# Heartbeat_sch.net
KiCad netlist of a schematic drawn in Altium Designer
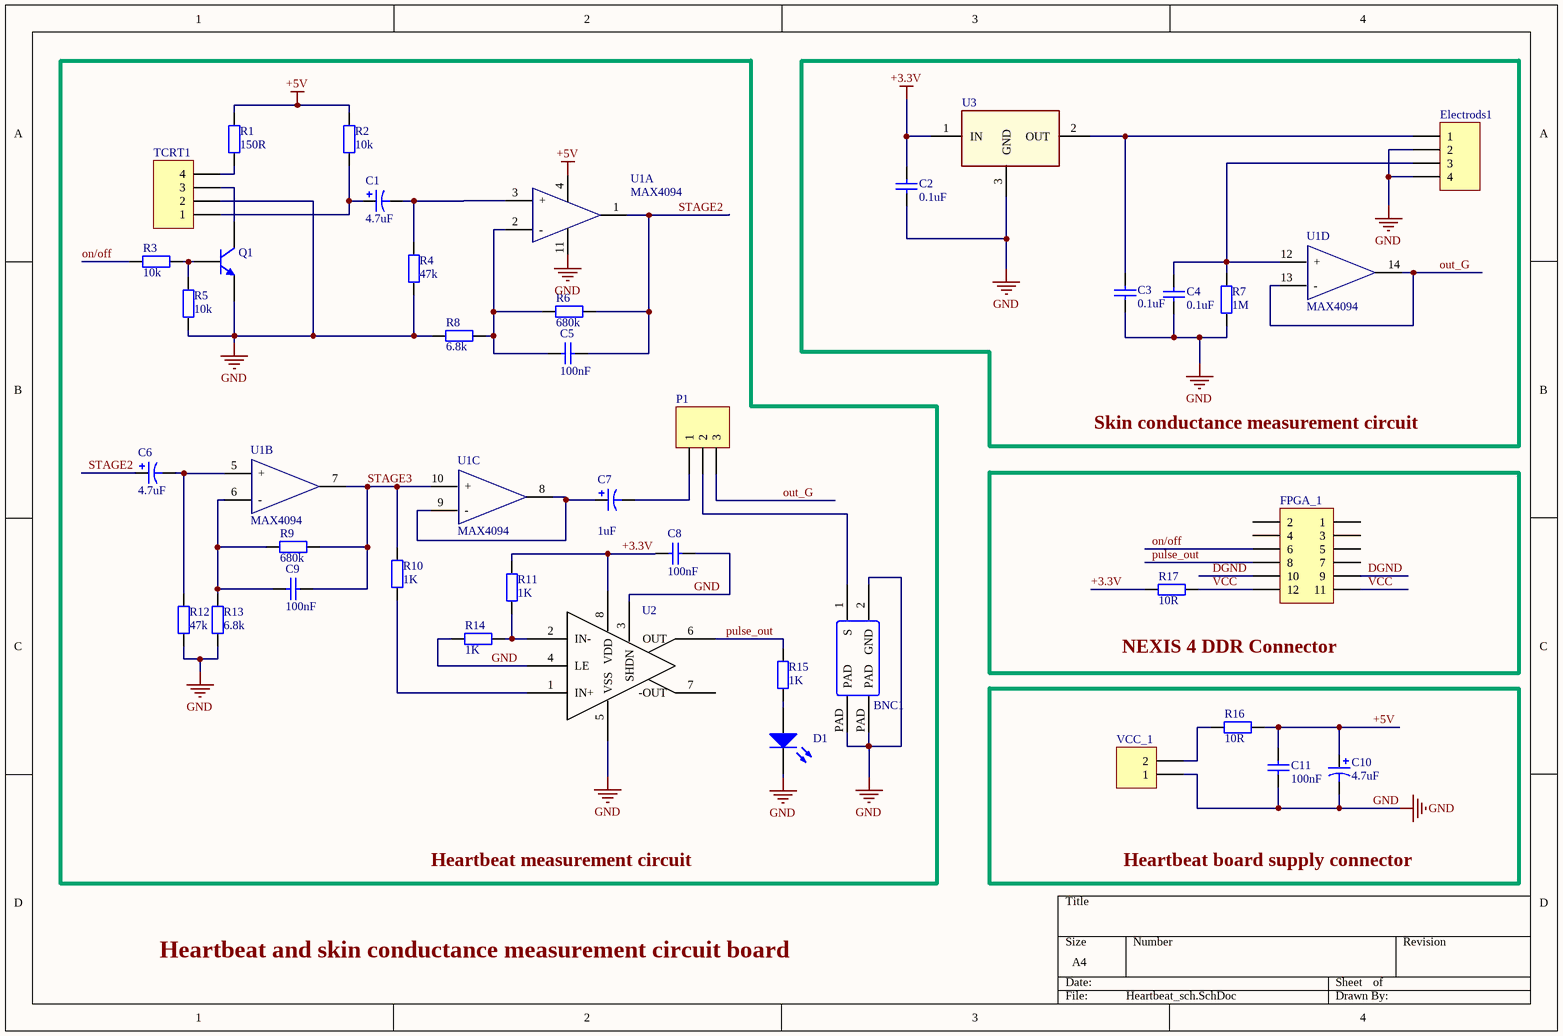
[diagram p0: Heartbeat_sch.SchDoc]

(export (version "E")
  (design (tool "Eeschema 10.0.6"))
  (components
    (comp (ref "BNC1")
      (value "BNC FEMALE CONN")
      (footprint "BNC CONNECTOR")
      (libsource (lib "BNC PCB CONN") (part "BNC FEMALE CONN"))
    )
    (comp (ref "C1")
      (value "4.7uF")
      (footprint "Condensator SMD tantal case A")
      (description "Polarized Capacitor (Radial)")
      (fields (field (name "Comment") "Cap Pol1") (field (name "PUBLISHER") "Altium Limited"))
      (libsource (lib "Miscellaneous Devices") (part "Cap Pol1"))
    )
    (comp (ref "C2")
      (value "0.1uF")
      (footprint "capacitor 2012[0805]:capacitor 2012[0805]")
      (description "Capacitor")
      (fields (field (name "Comment") "Cap") (field (name "PUBLISHER") "Altium Limited"))
      (libsource (lib "Miscellaneous Devices") (part "Cap"))
    )
    (comp (ref "C3")
      (value "0.1uF")
      (footprint "capacitor 2012[0805]:capacitor 2012[0805]")
      (description "Capacitor")
      (fields (field (name "Comment") "Cap") (field (name "PUBLISHER") "Altium Limited"))
      (libsource (lib "Miscellaneous Devices") (part "Cap"))
    )
    (comp (ref "C4")
      (value "0.1uF")
      (footprint "capacitor 2012[0805]:capacitor 2012[0805]")
      (description "Capacitor")
      (fields (field (name "Comment") "Cap") (field (name "PUBLISHER") "Altium Limited"))
      (libsource (lib "Miscellaneous Devices") (part "Cap"))
    )
    (comp (ref "C5")
      (value "100nF")
      (footprint "capacitor 2012[0805]:capacitor 2012[0805]")
      (description "Capacitor")
      (fields (field (name "Comment") "Cap") (field (name "PUBLISHER") "Altium Limited"))
      (libsource (lib "Miscellaneous Devices") (part "Cap"))
    )
    (comp (ref "C6")
      (value "4.7uF")
      (footprint "Condensator SMD tantal case A")
      (description "Polarized Capacitor (Radial)")
      (fields (field (name "Comment") "Cap Pol1") (field (name "PUBLISHER") "Altium Limited"))
      (libsource (lib "Miscellaneous Devices") (part "Cap Pol1"))
    )
    (comp (ref "C7")
      (value "1uF")
      (footprint "Condensator SMD tantal case A")
      (description "Polarized Capacitor (Radial)")
      (fields (field (name "Comment") "Cap Pol1") (field (name "PUBLISHER") "Altium Limited"))
      (libsource (lib "Miscellaneous Devices") (part "Cap Pol1"))
    )
    (comp (ref "C8")
      (value "100nF")
      (footprint "capacitor 2012[0805]:capacitor 2012[0805]")
      (description "Capacitor")
      (fields (field (name "Comment") "Cap") (field (name "PUBLISHER") "Altium Limited"))
      (libsource (lib "Miscellaneous Devices") (part "Cap"))
    )
    (comp (ref "C9")
      (value "100nF")
      (footprint "capacitor 2012[0805]:capacitor 2012[0805]")
      (description "Capacitor")
      (fields (field (name "Comment") "Cap") (field (name "PUBLISHER") "Altium Limited"))
      (libsource (lib "Miscellaneous Devices") (part "Cap"))
    )
    (comp (ref "C10")
      (value "4.7uF")
      (footprint "Condensator SMD tantal case A")
      (description "Polarized Capacitor (Radial)")
      (fields (field (name "Comment") "Cap Pol1") (field (name "PUBLISHER") "Altium Limited"))
      (libsource (lib "Miscellaneous Devices") (part "Cap Pol1"))
    )
    (comp (ref "C11")
      (value "100nF")
      (footprint "capacitor 2012[0805]:capacitor 2012[0805]")
      (description "Capacitor")
      (fields (field (name "Comment") "Cap") (field (name "PUBLISHER") "Altium Limited"))
      (libsource (lib "Miscellaneous Devices") (part "Cap"))
    )
    (comp (ref "D1")
      (value "LED0")
      (footprint "led smd verde:led smd verde")
      (description "Typical INFRARED GaAs LED")
      (fields (field (name "PUBLISHER") "Altium Limited"))
      (libsource (lib "Miscellaneous Devices") (part "LED0"))
    )
    (comp (ref "Electrods1")
      (value "Header 4H")
      (footprint "HDR1X4H")
      (description "Header, 4-Pin, Right Angle")
      (fields (field (name "PUBLISHER") "Altium Limited"))
      (libsource (lib "") (part "Header 4H_1"))
    )
    (comp (ref "FPGA_1")
      (value "Header 6X2H")
      (footprint "HDR2X6H")
      (description "Header, 6-Pin, Dual row, Right Angle")
      (fields (field (name "PUBLISHER") "Altium Limited"))
      (libsource (lib "Miscellaneous Connectors") (part "Header 6X2H"))
    )
    (comp (ref "P1")
      (value "Header 3")
      (footprint "hdr x3male:hdr3")
      (description "Header, 3-Pin")
      (fields (field (name "PUBLISHER") "Altium Limited"))
      (libsource (lib "Miscellaneous Connectors") (part "Header 3"))
    )
    (comp (ref "Q1")
      (value "2N3904")
      (footprint "SOT23-3M")
      (description "NPN General Purpose Amplifier")
      (fields (field (name "PUBLISHER") "Altium Limited"))
      (libsource (lib "Miscellaneous Devices") (part "2N3904"))
    )
    (comp (ref "R1")
      (value "150R")
      (footprint "2012 (Rezistor):2012(rezistor)")
      (description "Resistor")
      (fields (field (name "Comment") "Res2") (field (name "PUBLISHER") "Altium Limited"))
      (libsource (lib "") (part "Res2_1"))
    )
    (comp (ref "R2")
      (value "10k")
      (footprint "2012 (Rezistor):2012(rezistor)")
      (description "Resistor")
      (fields (field (name "Comment") "Res2") (field (name "PUBLISHER") "Altium Limited"))
      (libsource (lib "") (part "Res2_1"))
    )
    (comp (ref "R3")
      (value "10k")
      (footprint "2012 (Rezistor):2012(rezistor)")
      (description "Resistor")
      (fields (field (name "Comment") "Res2") (field (name "PUBLISHER") "Altium Limited"))
      (libsource (lib "Miscellaneous Devices") (part "Res2"))
    )
    (comp (ref "R4")
      (value "47k")
      (footprint "2012 (Rezistor):2012(rezistor)")
      (description "Resistor")
      (fields (field (name "Comment") "Res2") (field (name "PUBLISHER") "Altium Limited"))
      (libsource (lib "") (part "Res2_2"))
    )
    (comp (ref "R5")
      (value "10k")
      (footprint "2012 (Rezistor):2012(rezistor)")
      (description "Resistor")
      (fields (field (name "Comment") "Res2") (field (name "PUBLISHER") "Altium Limited"))
      (libsource (lib "") (part "Res2_1"))
    )
    (comp (ref "R6")
      (value "680k")
      (footprint "2012 (Rezistor):2012(rezistor)")
      (description "Resistor")
      (fields (field (name "Comment") "Res2") (field (name "PUBLISHER") "Altium Limited"))
      (libsource (lib "Miscellaneous Devices") (part "Res2"))
    )
    (comp (ref "R7")
      (value "1M")
      (footprint "2012 (Rezistor):2012(rezistor)")
      (description "Resistor")
      (fields (field (name "Comment") "Res2") (field (name "PUBLISHER") "Altium Limited"))
      (libsource (lib "") (part "Res2_1"))
    )
    (comp (ref "R8")
      (value "6.8k")
      (footprint "2012 (Rezistor):2012(rezistor)")
      (description "Resistor")
      (fields (field (name "Comment") "Res2") (field (name "PUBLISHER") "Altium Limited"))
      (libsource (lib "Miscellaneous Devices") (part "Res2"))
    )
    (comp (ref "R9")
      (value "680k")
      (footprint "2012 (Rezistor):2012(rezistor)")
      (description "Resistor")
      (fields (field (name "Comment") "Res2") (field (name "PUBLISHER") "Altium Limited"))
      (libsource (lib "Miscellaneous Devices") (part "Res2"))
    )
    (comp (ref "R10")
      (value "1K")
      (footprint "2012 (Rezistor):2012(rezistor)")
      (description "Resistor")
      (fields (field (name "Comment") "Res2") (field (name "PUBLISHER") "Altium Limited"))
      (libsource (lib "") (part "Res2_2"))
    )
    (comp (ref "R11")
      (value "1K")
      (footprint "2012 (Rezistor):2012(rezistor)")
      (description "Resistor")
      (fields (field (name "Comment") "Res2") (field (name "PUBLISHER") "Altium Limited"))
      (libsource (lib "") (part "Res2_2"))
    )
    (comp (ref "R12")
      (value "47k")
      (footprint "2012 (Rezistor):2012(rezistor)")
      (description "Resistor")
      (fields (field (name "Comment") "Res2") (field (name "PUBLISHER") "Altium Limited"))
      (libsource (lib "") (part "Res2_2"))
    )
    (comp (ref "R13")
      (value "6.8k")
      (footprint "2012 (Rezistor):2012(rezistor)")
      (description "Resistor")
      (fields (field (name "Comment") "Res2") (field (name "PUBLISHER") "Altium Limited"))
      (libsource (lib "") (part "Res2_1"))
    )
    (comp (ref "R14")
      (value "1K")
      (footprint "2012 (Rezistor):2012(rezistor)")
      (description "Resistor")
      (fields (field (name "Comment") "Res2") (field (name "PUBLISHER") "Altium Limited"))
      (libsource (lib "") (part "Res2_3"))
    )
    (comp (ref "R15")
      (value "1K")
      (footprint "2012 (Rezistor):2012(rezistor)")
      (description "Resistor")
      (fields (field (name "Comment") "Res2") (field (name "PUBLISHER") "Altium Limited"))
      (libsource (lib "") (part "Res2_2"))
    )
    (comp (ref "R16")
      (value "10R")
      (footprint "2012 (Rezistor):2012(rezistor)")
      (description "Resistor")
      (fields (field (name "Comment") "Res2") (field (name "PUBLISHER") "Altium Limited"))
      (libsource (lib "Miscellaneous Devices") (part "Res2"))
    )
    (comp (ref "R17")
      (value "10R")
      (footprint "2012 (Rezistor):2012(rezistor)")
      (description "Resistor")
      (fields (field (name "Comment") "Res2") (field (name "PUBLISHER") "Altium Limited"))
      (libsource (lib "Miscellaneous Devices") (part "Res2"))
    )
    (comp (ref "TCRT1")
      (value "Header 4H")
      (footprint "HDR1X4H")
      (description "Header, 4-Pin, Right Angle")
      (fields (field (name "PUBLISHER") "Altium Limited"))
      (libsource (lib "Miscellaneous Connectors") (part "Header 4H"))
    )
    (comp (ref "U1")
      (value "MAX4094")
      (footprint "SOIC127P600-14M")
      (libsource (lib "Schlib1") (part "MAX4094"))
    )
    (comp (ref "U2")
      (value "Component_1")
      (footprint "SOIC 8 pini")
      (libsource (lib "MAX961") (part "Component_1"))
    )
    (comp (ref "U3")
      (value "MAX6061")
      (footprint "Maxim Power Mgt Voltage Reference:SOT23-3_L")
      (description "Precision, Micropower, Low-Dropout,  High-Output-Current, SOT23 Voltage References")
      (libsource (lib "MAX6061") (part "MAX6061"))
    )
    (comp (ref "VCC_1")
      (value "Header 2")
      (footprint "HDR1X2")
      (description "Header, 2-Pin")
      (fields (field (name "PUBLISHER") "Altium Limited"))
      (libsource (lib "Miscellaneous Connectors") (part "Header 2"))
    )
  )
  (nets
    (net (code "1") (name "+3.3V") (class "Default")
      (node (ref "C2") (pin "2") (pinfunction "2_2") (pintype "passive"))
      (node (ref "C8") (pin "2") (pinfunction "2_2") (pintype "passive"))
      (node (ref "R11") (pin "1") (pinfunction "1_1") (pintype "passive"))
      (node (ref "R17") (pin "2") (pinfunction "2_2") (pintype "passive"))
      (node (ref "U2") (pin "8") (pinfunction "VDD_8") (pintype "passive"))
      (node (ref "U3") (pin "1") (pinfunction "IN_1") (pintype "passive"))
    )
    (net (code "2") (name "+5V") (class "Default")
      (node (ref "C10") (pin "1") (pinfunction "1_1") (pintype "passive"))
      (node (ref "C11") (pin "1") (pinfunction "1_1") (pintype "passive"))
      (node (ref "R1") (pin "2") (pinfunction "2_2") (pintype "passive"))
      (node (ref "R16") (pin "1") (pinfunction "1_1") (pintype "passive"))
      (node (ref "R2") (pin "2") (pinfunction "2_2") (pintype "passive"))
      (node (ref "U1") (pin "4") (pintype "passive"))
    )
    (net (code "3") (name "/DGND") (class "Default")
      (node (ref "FPGA_1") (pin "10") (pinfunction "10_10") (pintype "passive"))
      (node (ref "FPGA_1") (pin "9") (pinfunction "9_9") (pintype "passive"))
    )
    (net (code "4") (name "/STAGE2") (class "Default")
      (node (ref "C5") (pin "2") (pinfunction "2_2") (pintype "passive"))
      (node (ref "C6") (pin "1") (pinfunction "1_1") (pintype "passive"))
      (node (ref "R6") (pin "1") (pinfunction "1_1") (pintype "passive"))
      (node (ref "U1") (pin "1") (pinfunction "OUT_1") (pintype "passive"))
    )
    (net (code "5") (name "/STAGE3") (class "Default")
      (node (ref "C9") (pin "1") (pinfunction "1_1") (pintype "passive"))
      (node (ref "R10") (pin "1") (pinfunction "1_1") (pintype "passive"))
      (node (ref "R9") (pin "1") (pinfunction "1_1") (pintype "passive"))
      (node (ref "U1") (pin "10") (pinfunction "+_10") (pintype "passive"))
      (node (ref "U1") (pin "7") (pinfunction "OUT_7") (pintype "passive"))
    )
    (net (code "6") (name "/VCC") (class "Default")
      (node (ref "FPGA_1") (pin "11") (pinfunction "11_11") (pintype "passive"))
      (node (ref "FPGA_1") (pin "12") (pinfunction "12_12") (pintype "passive"))
      (node (ref "R17") (pin "1") (pinfunction "1_1") (pintype "passive"))
    )
    (net (code "7") (name "/on{slash}off") (class "Default")
      (node (ref "FPGA_1") (pin "6") (pinfunction "6_6") (pintype "passive"))
      (node (ref "R3") (pin "2") (pinfunction "2_2") (pintype "passive"))
    )
    (net (code "8") (name "/out_G") (class "Default")
      (node (ref "P1") (pin "3") (pinfunction "3_3") (pintype "passive"))
      (node (ref "U1") (pin "13") (pinfunction "-_13") (pintype "passive"))
      (node (ref "U1") (pin "14") (pinfunction "OUT_14") (pintype "passive"))
    )
    (net (code "9") (name "/pulse_out") (class "Default")
      (node (ref "FPGA_1") (pin "8") (pinfunction "8_8") (pintype "passive"))
      (node (ref "R15") (pin "1") (pinfunction "1_1") (pintype "passive"))
      (node (ref "U2") (pin "6") (pinfunction "OUT_6") (pintype "passive"))
    )
    (net (code "10") (name "GND") (class "Default")
      (node (ref "BNC1") (pin "2") (pinfunction "GND_2") (pintype "passive"))
      (node (ref "BNC1") (pin "PAD") (pinfunction "PAD_PAD") (pintype "passive"))
      (node (ref "C10") (pin "2") (pinfunction "2_2") (pintype "passive"))
      (node (ref "C11") (pin "2") (pinfunction "2_2") (pintype "passive"))
      (node (ref "C2") (pin "1") (pinfunction "1_1") (pintype "passive"))
      (node (ref "C3") (pin "1") (pinfunction "1_1") (pintype "passive"))
      (node (ref "C4") (pin "1") (pinfunction "1_1") (pintype "passive"))
      (node (ref "C8") (pin "1") (pinfunction "1_1") (pintype "passive"))
      (node (ref "D1") (pin "2") (pinfunction "K_2") (pintype "passive"))
      (node (ref "Electrods1") (pin "2") (pinfunction "2_2") (pintype "passive"))
      (node (ref "Electrods1") (pin "4") (pinfunction "4_4") (pintype "passive"))
      (node (ref "Q1") (pin "1") (pinfunction "E_1") (pintype "passive"))
      (node (ref "R12") (pin "2") (pinfunction "2_2") (pintype "passive"))
      (node (ref "R13") (pin "1") (pinfunction "1_1") (pintype "passive"))
      (node (ref "R14") (pin "1") (pinfunction "1_1") (pintype "passive"))
      (node (ref "R4") (pin "2") (pinfunction "2_2") (pintype "passive"))
      (node (ref "R5") (pin "1") (pinfunction "1_1") (pintype "passive"))
      (node (ref "R7") (pin "1") (pinfunction "1_1") (pintype "passive"))
      (node (ref "R8") (pin "2") (pinfunction "2_2") (pintype "passive"))
      (node (ref "TCRT1") (pin "2") (pinfunction "2_2") (pintype "passive"))
      (node (ref "U1") (pin "11") (pinfunction "11_11") (pintype "passive"))
      (node (ref "U2") (pin "3") (pinfunction "SHDN_3") (pintype "passive"))
      (node (ref "U2") (pin "4") (pinfunction "LE_4") (pintype "passive"))
      (node (ref "U2") (pin "5") (pinfunction "VSS_5") (pintype "passive"))
      (node (ref "U3") (pin "3") (pinfunction "GND_3") (pintype "passive"))
      (node (ref "VCC_1") (pin "1") (pinfunction "1_1") (pintype "passive"))
    )
    (net (code "11") (name "Net-(BNC1-S)") (class "Default")
      (node (ref "BNC1") (pin "1") (pinfunction "S_1") (pintype "passive"))
      (node (ref "P1") (pin "2") (pinfunction "2_2") (pintype "passive"))
    )
    (net (code "12") (name "Net-(C1-Pad1)") (class "Default")
      (node (ref "C1") (pin "1") (pinfunction "1_1") (pintype "passive"))
      (node (ref "R2") (pin "1") (pinfunction "1_1") (pintype "passive"))
      (node (ref "TCRT1") (pin "1") (pinfunction "1_1") (pintype "passive"))
    )
    (net (code "13") (name "Net-(C7-Pad2)") (class "Default")
      (node (ref "C7") (pin "2") (pinfunction "2_2") (pintype "passive"))
      (node (ref "P1") (pin "1") (pinfunction "1_1") (pintype "passive"))
    )
    (net (code "14") (name "Net-(D1-A)") (class "Default")
      (node (ref "D1") (pin "1") (pinfunction "A_1") (pintype "passive"))
      (node (ref "R15") (pin "2") (pinfunction "2_2") (pintype "passive"))
    )
    (net (code "15") (name "Net-(Q1-B)") (class "Default")
      (node (ref "Q1") (pin "2") (pinfunction "B_2") (pintype "passive"))
      (node (ref "R3") (pin "1") (pinfunction "1_1") (pintype "passive"))
      (node (ref "R5") (pin "2") (pinfunction "2_2") (pintype "passive"))
    )
    (net (code "16") (name "Net-(Q1-C)") (class "Default")
      (node (ref "Q1") (pin "3") (pinfunction "C_3") (pintype "passive"))
      (node (ref "TCRT1") (pin "3") (pinfunction "3_3") (pintype "passive"))
    )
    (net (code "17") (name "Net-(R1-Pad1)") (class "Default")
      (node (ref "R1") (pin "1") (pinfunction "1_1") (pintype "passive"))
      (node (ref "TCRT1") (pin "4") (pinfunction "4_4") (pintype "passive"))
    )
    (net (code "18") (name "Net-(R16-Pad2)") (class "Default")
      (node (ref "R16") (pin "2") (pinfunction "2_2") (pintype "passive"))
      (node (ref "VCC_1") (pin "2") (pinfunction "2_2") (pintype "passive"))
    )
    (net (code "19") (name "Net-(U1A-+)") (class "Default")
      (node (ref "C1") (pin "2") (pinfunction "2_2") (pintype "passive"))
      (node (ref "R4") (pin "1") (pinfunction "1_1") (pintype "passive"))
      (node (ref "U1") (pin "3") (pinfunction "+_3") (pintype "passive"))
    )
    (net (code "20") (name "Net-(U1A--)") (class "Default")
      (node (ref "C5") (pin "1") (pinfunction "1_1") (pintype "passive"))
      (node (ref "R6") (pin "2") (pinfunction "2_2") (pintype "passive"))
      (node (ref "R8") (pin "1") (pinfunction "1_1") (pintype "passive"))
      (node (ref "U1") (pin "2") (pinfunction "-_2") (pintype "passive"))
    )
    (net (code "21") (name "Net-(U1B-+)") (class "Default")
      (node (ref "C6") (pin "2") (pinfunction "2_2") (pintype "passive"))
      (node (ref "R12") (pin "1") (pinfunction "1_1") (pintype "passive"))
      (node (ref "U1") (pin "5") (pinfunction "+_5") (pintype "passive"))
    )
    (net (code "22") (name "Net-(U1B--)") (class "Default")
      (node (ref "C9") (pin "2") (pinfunction "2_2") (pintype "passive"))
      (node (ref "R13") (pin "2") (pinfunction "2_2") (pintype "passive"))
      (node (ref "R9") (pin "2") (pinfunction "2_2") (pintype "passive"))
      (node (ref "U1") (pin "6") (pinfunction "-_6") (pintype "passive"))
    )
    (net (code "23") (name "Net-(U1C--)") (class "Default")
      (node (ref "C7") (pin "1") (pinfunction "1_1") (pintype "passive"))
      (node (ref "U1") (pin "8") (pinfunction "OUT_8") (pintype "passive"))
      (node (ref "U1") (pin "9") (pinfunction "-_9") (pintype "passive"))
    )
    (net (code "24") (name "Net-(U1D-+)") (class "Default")
      (node (ref "C4") (pin "2") (pinfunction "2_2") (pintype "passive"))
      (node (ref "Electrods1") (pin "3") (pinfunction "3_3") (pintype "passive"))
      (node (ref "R7") (pin "2") (pinfunction "2_2") (pintype "passive"))
      (node (ref "U1") (pin "12") (pinfunction "+_12") (pintype "passive"))
    )
    (net (code "25") (name "Net-(U2-IN+)") (class "Default")
      (node (ref "R10") (pin "2") (pinfunction "2_2") (pintype "passive"))
      (node (ref "U2") (pin "1") (pinfunction "IN+_1") (pintype "passive"))
    )
    (net (code "26") (name "Net-(U2-IN-)") (class "Default")
      (node (ref "R11") (pin "2") (pinfunction "2_2") (pintype "passive"))
      (node (ref "R14") (pin "2") (pinfunction "2_2") (pintype "passive"))
      (node (ref "U2") (pin "2") (pinfunction "IN-_2") (pintype "passive"))
    )
    (net (code "27") (name "Net-(U3-OUT)") (class "Default")
      (node (ref "C3") (pin "2") (pinfunction "2_2") (pintype "passive"))
      (node (ref "Electrods1") (pin "1") (pinfunction "1_1") (pintype "passive"))
      (node (ref "U3") (pin "2") (pinfunction "OUT_2") (pintype "passive"))
    )
    (net (code "28") (name "unconnected-(FPGA_1-Pad1)") (class "Default")
      (node (ref "FPGA_1") (pin "1") (pinfunction "1_1") (pintype "passive"))
    )
    (net (code "29") (name "unconnected-(FPGA_1-Pad2)") (class "Default")
      (node (ref "FPGA_1") (pin "2") (pinfunction "2_2") (pintype "passive"))
    )
    (net (code "30") (name "unconnected-(FPGA_1-Pad3)") (class "Default")
      (node (ref "FPGA_1") (pin "3") (pinfunction "3_3") (pintype "passive"))
    )
    (net (code "31") (name "unconnected-(FPGA_1-Pad4)") (class "Default")
      (node (ref "FPGA_1") (pin "4") (pinfunction "4_4") (pintype "passive"))
    )
    (net (code "32") (name "unconnected-(FPGA_1-Pad5)") (class "Default")
      (node (ref "FPGA_1") (pin "5") (pinfunction "5_5") (pintype "passive"))
    )
    (net (code "33") (name "unconnected-(FPGA_1-Pad7)") (class "Default")
      (node (ref "FPGA_1") (pin "7") (pinfunction "7_7") (pintype "passive"))
    )
    (net (code "34") (name "unconnected-(U2--OUT-Pad7)") (class "Default")
      (node (ref "U2") (pin "7") (pinfunction "-OUT_7") (pintype "passive"))
    )
  )
)
